# I2CIsoBreakoutV01.net
KiCad netlist of a schematic drawn in EAGLE
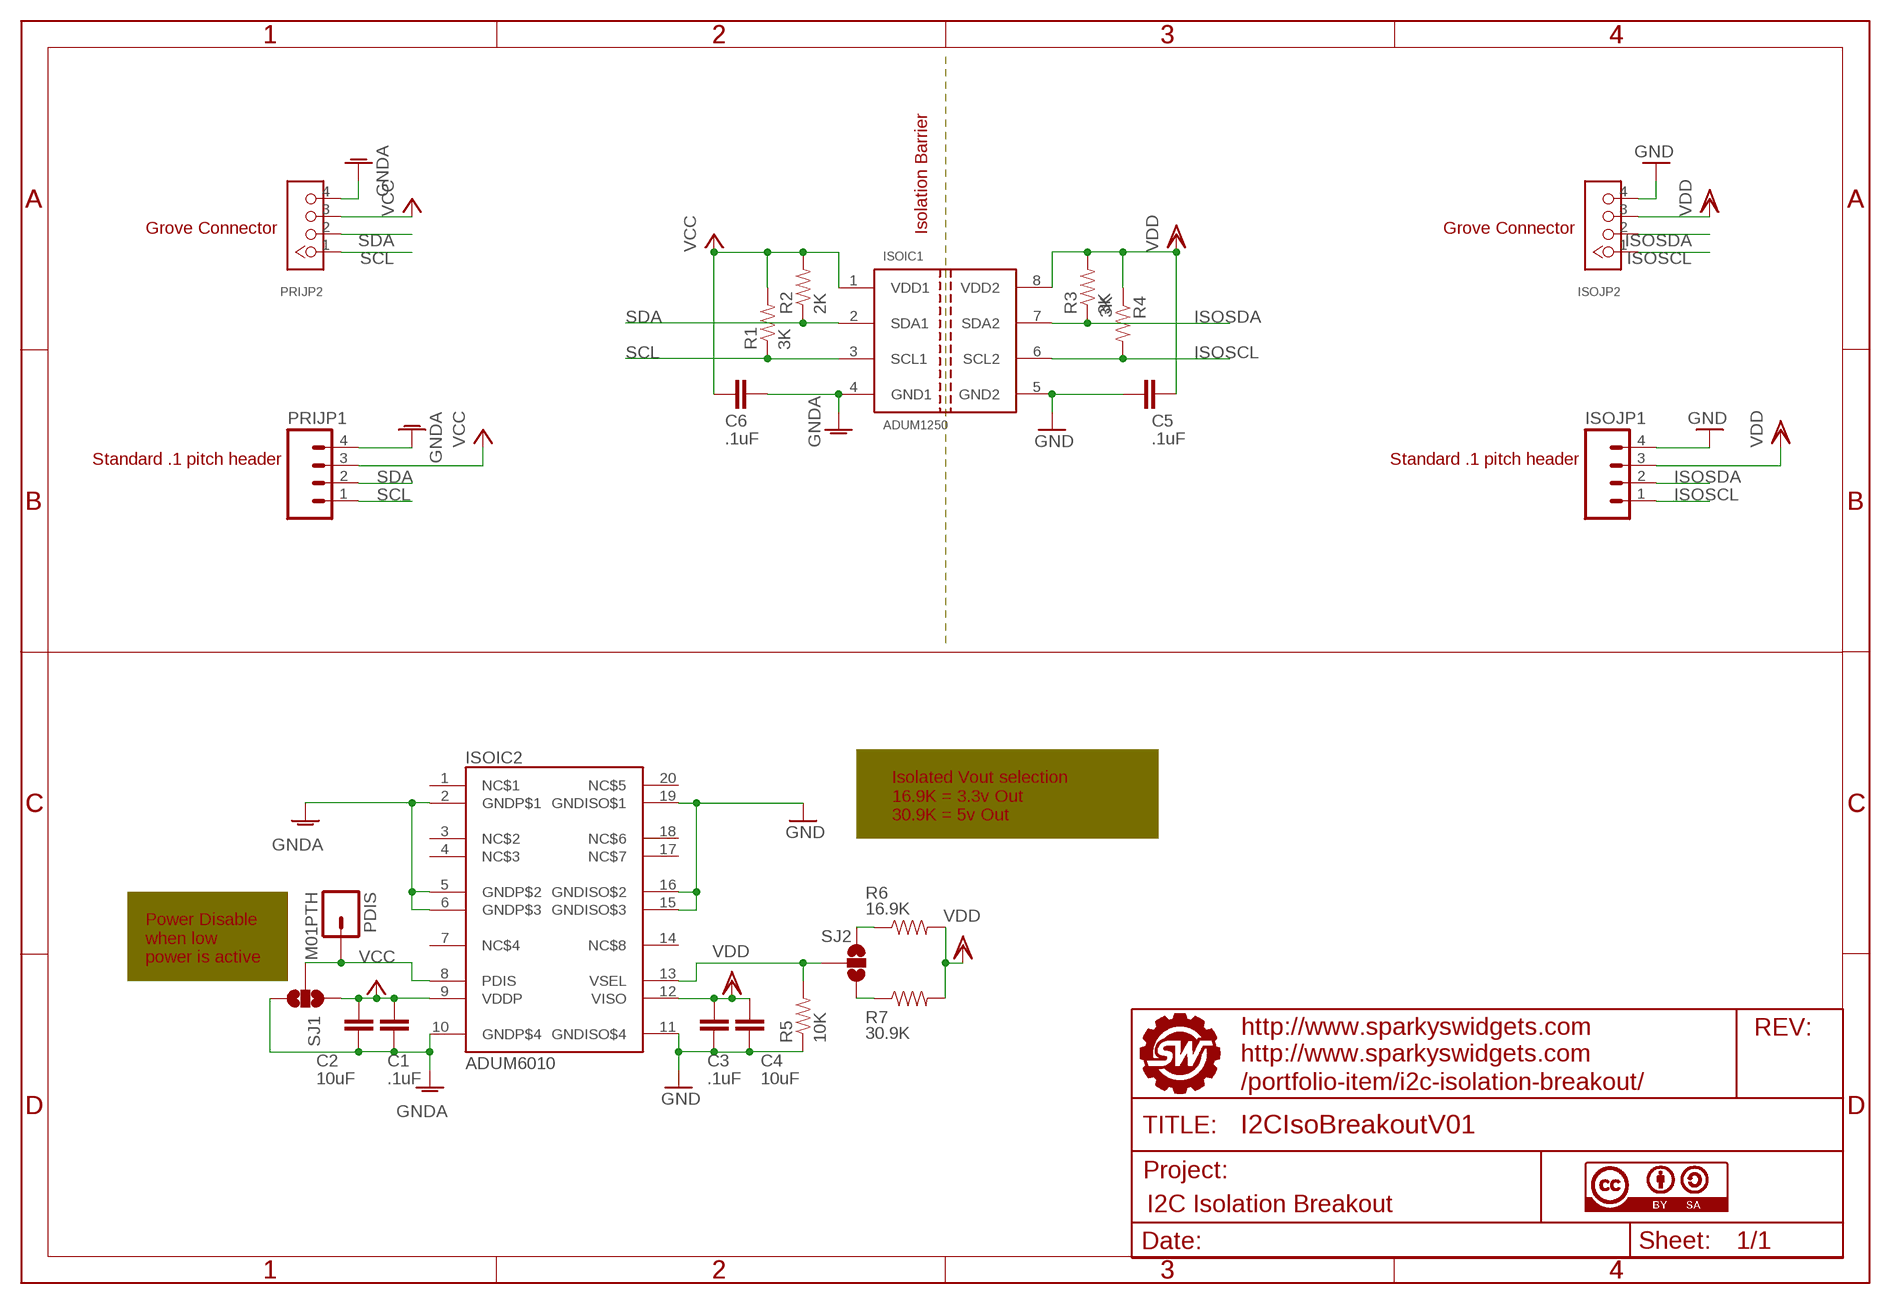
[diagram p0: schematic, sheet 1]

(export (version "E")
  (design (tool "Eeschema 10.0.6"))
  (components
    (comp (ref "C1")
      (value ".1uF")
      (footprint "eagle-import:0805")
      (libsource (lib "eagle-import") (part "CAP0805"))
    )
    (comp (ref "C2")
      (value "10uF")
      (footprint "eagle-import:0805")
      (libsource (lib "eagle-import") (part "CAP0805"))
    )
    (comp (ref "C3")
      (value ".1uF")
      (footprint "eagle-import:0805")
      (libsource (lib "eagle-import") (part "CAP0805"))
    )
    (comp (ref "C4")
      (value "10uF")
      (footprint "eagle-import:0805")
      (libsource (lib "eagle-import") (part "CAP0805"))
    )
    (comp (ref "C5")
      (value ".1uF")
      (footprint "eagle-import:0805")
      (libsource (lib "eagle-import") (part "CAP0805"))
    )
    (comp (ref "C6")
      (value ".1uF")
      (footprint "eagle-import:0805")
      (libsource (lib "eagle-import") (part "CAP0805"))
    )
    (comp (ref "ISOIC1")
      (value "ADUM1250")
      (footprint "eagle-import:SO08")
      (libsource (lib "eagle-import") (part "ADUM1250"))
    )
    (comp (ref "ISOIC2")
      (value "ADUM6010")
      (footprint "eagle-import:SSOP20")
      (libsource (lib "eagle-import") (part "ADUM6010"))
    )
    (comp (ref "ISOJP1")
      (value "M04PTH")
      (footprint "eagle-import:1X04")
      (libsource (lib "eagle-import") (part "M04PTH"))
    )
    (comp (ref "ISOJP2")
      (value "TWIG-4P-2.0-2.0")
      (footprint "eagle-import:4P-2.0")
      (libsource (lib "eagle-import") (part "TWIG-4P-2.0-2.0"))
    )
    (comp (ref "PDIS")
      (value "M01PTH")
      (footprint "eagle-import:1X01")
      (libsource (lib "eagle-import") (part "M01PTH"))
    )
    (comp (ref "PRIJP1")
      (value "M04PTH")
      (footprint "eagle-import:1X04")
      (libsource (lib "eagle-import") (part "M04PTH"))
    )
    (comp (ref "PRIJP2")
      (value "TWIG-4P-2.0-2.0")
      (footprint "eagle-import:4P-2.0")
      (libsource (lib "eagle-import") (part "TWIG-4P-2.0-2.0"))
    )
    (comp (ref "R1")
      (value "3K")
      (footprint "eagle-import:0805")
      (libsource (lib "eagle-import") (part "RESISTOR0805-RES"))
    )
    (comp (ref "R2")
      (value "2K")
      (footprint "eagle-import:0805")
      (libsource (lib "eagle-import") (part "RESISTOR0805-RES"))
    )
    (comp (ref "R3")
      (value "3K")
      (footprint "eagle-import:0805")
      (libsource (lib "eagle-import") (part "RESISTOR0805-RES"))
    )
    (comp (ref "R4")
      (value "3K")
      (footprint "eagle-import:0805")
      (libsource (lib "eagle-import") (part "RESISTOR0805-RES"))
    )
    (comp (ref "R5")
      (value "10K")
      (footprint "eagle-import:0805")
      (libsource (lib "eagle-import") (part "RESISTOR0805-RES"))
    )
    (comp (ref "R6")
      (value "16.9K")
      (footprint "eagle-import:0805")
      (libsource (lib "eagle-import") (part "RESISTOR0805-RES"))
    )
    (comp (ref "R7")
      (value "30.9K")
      (footprint "eagle-import:0805")
      (libsource (lib "eagle-import") (part "RESISTOR0805-RES"))
    )
    (comp (ref "SJ1")
      (value "SOLDERJUMPER_2WAYPASTE2&3")
      (footprint "eagle-import:SJ_3_PASTE2&3")
      (libsource (lib "eagle-import") (part "SOLDERJUMPER_2WAYPASTE2&3"))
    )
    (comp (ref "SJ2")
      (value "SOLDERJUMPER_2WAYPASTE2&3")
      (footprint "eagle-import:SJ_3_PASTE2&3")
      (libsource (lib "eagle-import") (part "SOLDERJUMPER_2WAYPASTE2&3"))
    )
    (comp (ref "U$1")
      (value "FRAME_ISOI2CBREAKOUT")
      (footprint "eagle-import:SWPCBLOGOWITHINFO")
      (libsource (lib "eagle-import") (part "FRAME_ISOI2CBREAKOUT"))
    )
    (comp (ref "U$2")
      (value "CC-BY-SA")
      (footprint "eagle-import:CC-BY-SA")
      (libsource (lib "eagle-import") (part "CC-BY-SA"))
    )
  )
  (nets
    (net (code "1") (name "/ISOSCL") (class "Default")
      (node (ref "ISOIC1") (pin "6") (pinfunction "SCL2_6") (pintype "bidirectional"))
      (node (ref "ISOJP1") (pin "1") (pinfunction "1_1") (pintype "passive"))
      (node (ref "ISOJP2") (pin "1") (pinfunction "1_1") (pintype "bidirectional"))
      (node (ref "R4") (pin "2") (pinfunction "2_2") (pintype "passive"))
    )
    (net (code "2") (name "/ISOSDA") (class "Default")
      (node (ref "ISOIC1") (pin "7") (pinfunction "SDA2_7") (pintype "bidirectional"))
      (node (ref "ISOJP1") (pin "2") (pinfunction "2_2") (pintype "passive"))
      (node (ref "ISOJP2") (pin "2") (pinfunction "2_2") (pintype "bidirectional"))
      (node (ref "R3") (pin "1") (pinfunction "1_1") (pintype "passive"))
    )
    (net (code "3") (name "/SCL") (class "Default")
      (node (ref "ISOIC1") (pin "3") (pinfunction "SCL1_3") (pintype "bidirectional"))
      (node (ref "PRIJP1") (pin "1") (pinfunction "1_1") (pintype "passive"))
      (node (ref "PRIJP2") (pin "1") (pinfunction "1_1") (pintype "bidirectional"))
      (node (ref "R1") (pin "1") (pinfunction "1_1") (pintype "passive"))
    )
    (net (code "4") (name "/SDA") (class "Default")
      (node (ref "ISOIC1") (pin "2") (pinfunction "SDA1_2") (pintype "bidirectional"))
      (node (ref "PRIJP1") (pin "2") (pinfunction "2_2") (pintype "passive"))
      (node (ref "PRIJP2") (pin "2") (pinfunction "2_2") (pintype "bidirectional"))
      (node (ref "R2") (pin "1") (pinfunction "1_1") (pintype "passive"))
    )
    (net (code "5") (name "GND") (class "Default")
      (node (ref "C3") (pin "2") (pinfunction "2_2") (pintype "passive"))
      (node (ref "C4") (pin "2") (pinfunction "2_2") (pintype "passive"))
      (node (ref "C5") (pin "1") (pinfunction "1_1") (pintype "passive"))
      (node (ref "ISOIC1") (pin "5") (pinfunction "GND2_5") (pintype "power_in"))
      (node (ref "ISOIC2") (pin "11") (pinfunction "GNDISO$4_11") (pintype "power_in"))
      (node (ref "ISOIC2") (pin "15") (pinfunction "GNDISO$3_15") (pintype "power_in"))
      (node (ref "ISOIC2") (pin "16") (pinfunction "GNDISO$2_16") (pintype "power_in"))
      (node (ref "ISOIC2") (pin "19") (pinfunction "GNDISO$1_19") (pintype "power_in"))
      (node (ref "ISOJP1") (pin "4") (pinfunction "4_4") (pintype "passive"))
      (node (ref "ISOJP2") (pin "4") (pinfunction "4_4") (pintype "bidirectional"))
      (node (ref "R5") (pin "1") (pinfunction "1_1") (pintype "passive"))
    )
    (net (code "6") (name "GNDA") (class "Default")
      (node (ref "C1") (pin "2") (pinfunction "2_2") (pintype "passive"))
      (node (ref "C2") (pin "2") (pinfunction "2_2") (pintype "passive"))
      (node (ref "C6") (pin "1") (pinfunction "1_1") (pintype "passive"))
      (node (ref "ISOIC1") (pin "4") (pinfunction "GND1_4") (pintype "power_in"))
      (node (ref "ISOIC2") (pin "10") (pinfunction "GNDP$4_10") (pintype "power_in"))
      (node (ref "ISOIC2") (pin "2") (pinfunction "GNDP$1_2") (pintype "power_in"))
      (node (ref "ISOIC2") (pin "5") (pinfunction "GNDP$2_5") (pintype "power_in"))
      (node (ref "ISOIC2") (pin "6") (pinfunction "GNDP$3_6") (pintype "power_in"))
      (node (ref "PRIJP1") (pin "4") (pinfunction "4_4") (pintype "passive"))
      (node (ref "PRIJP2") (pin "4") (pinfunction "4_4") (pintype "bidirectional"))
      (node (ref "SJ1") (pin "3") (pinfunction "3_3") (pintype "passive"))
    )
    (net (code "7") (name "Net-(ISOIC2-PDIS)") (class "Default")
      (node (ref "ISOIC2") (pin "8") (pinfunction "PDIS_8") (pintype "input"))
      (node (ref "PDIS") (pin "1") (pinfunction "1_1") (pintype "passive"))
      (node (ref "SJ1") (pin "2") (pinfunction "2_2") (pintype "passive"))
    )
    (net (code "8") (name "Net-(ISOIC2-VSEL)") (class "Default")
      (node (ref "ISOIC2") (pin "13") (pinfunction "VSEL_13") (pintype "input"))
      (node (ref "R5") (pin "2") (pinfunction "2_2") (pintype "passive"))
      (node (ref "SJ2") (pin "2") (pinfunction "2_2") (pintype "passive"))
    )
    (net (code "9") (name "Net-(R6-Pad1)") (class "Default")
      (node (ref "R6") (pin "1") (pinfunction "1_1") (pintype "passive"))
      (node (ref "SJ2") (pin "1") (pinfunction "1_1") (pintype "passive"))
    )
    (net (code "10") (name "Net-(R7-Pad1)") (class "Default")
      (node (ref "R7") (pin "1") (pinfunction "1_1") (pintype "passive"))
      (node (ref "SJ2") (pin "3") (pinfunction "3_3") (pintype "passive"))
    )
    (net (code "11") (name "VCC") (class "Default")
      (node (ref "C1") (pin "1") (pinfunction "1_1") (pintype "passive"))
      (node (ref "C2") (pin "1") (pinfunction "1_1") (pintype "passive"))
      (node (ref "C6") (pin "2") (pinfunction "2_2") (pintype "passive"))
      (node (ref "ISOIC1") (pin "1") (pinfunction "VDD1_1") (pintype "power_in"))
      (node (ref "ISOIC2") (pin "9") (pinfunction "VDDP_9") (pintype "power_in"))
      (node (ref "PRIJP1") (pin "3") (pinfunction "3_3") (pintype "passive"))
      (node (ref "PRIJP2") (pin "3") (pinfunction "3_3") (pintype "bidirectional"))
      (node (ref "R1") (pin "2") (pinfunction "2_2") (pintype "passive"))
      (node (ref "R2") (pin "2") (pinfunction "2_2") (pintype "passive"))
      (node (ref "SJ1") (pin "1") (pinfunction "1_1") (pintype "passive"))
    )
    (net (code "12") (name "VDD") (class "Default")
      (node (ref "C3") (pin "1") (pinfunction "1_1") (pintype "passive"))
      (node (ref "C4") (pin "1") (pinfunction "1_1") (pintype "passive"))
      (node (ref "C5") (pin "2") (pinfunction "2_2") (pintype "passive"))
      (node (ref "ISOIC1") (pin "8") (pinfunction "VDD2_8") (pintype "power_in"))
      (node (ref "ISOIC2") (pin "12") (pinfunction "VISO_12") (pintype "power_in"))
      (node (ref "ISOJP1") (pin "3") (pinfunction "3_3") (pintype "passive"))
      (node (ref "ISOJP2") (pin "3") (pinfunction "3_3") (pintype "bidirectional"))
      (node (ref "R3") (pin "2") (pinfunction "2_2") (pintype "passive"))
      (node (ref "R4") (pin "1") (pinfunction "1_1") (pintype "passive"))
      (node (ref "R6") (pin "2") (pinfunction "2_2") (pintype "passive"))
      (node (ref "R7") (pin "2") (pinfunction "2_2") (pintype "passive"))
    )
    (net (code "13") (name "unconnected-(ISOIC2-NC$1-Pad1)") (class "Default")
      (node (ref "ISOIC2") (pin "1") (pinfunction "NC$1_1") (pintype "no_connect"))
    )
    (net (code "14") (name "unconnected-(ISOIC2-NC$2-Pad3)") (class "Default")
      (node (ref "ISOIC2") (pin "3") (pinfunction "NC$2_3") (pintype "no_connect"))
    )
    (net (code "15") (name "unconnected-(ISOIC2-NC$3-Pad4)") (class "Default")
      (node (ref "ISOIC2") (pin "4") (pinfunction "NC$3_4") (pintype "no_connect"))
    )
    (net (code "16") (name "unconnected-(ISOIC2-NC$4-Pad7)") (class "Default")
      (node (ref "ISOIC2") (pin "7") (pinfunction "NC$4_7") (pintype "no_connect"))
    )
    (net (code "17") (name "unconnected-(ISOIC2-NC$5-Pad20)") (class "Default")
      (node (ref "ISOIC2") (pin "20") (pinfunction "NC$5_20") (pintype "no_connect"))
    )
    (net (code "18") (name "unconnected-(ISOIC2-NC$6-Pad18)") (class "Default")
      (node (ref "ISOIC2") (pin "18") (pinfunction "NC$6_18") (pintype "no_connect"))
    )
    (net (code "19") (name "unconnected-(ISOIC2-NC$7-Pad17)") (class "Default")
      (node (ref "ISOIC2") (pin "17") (pinfunction "NC$7_17") (pintype "no_connect"))
    )
    (net (code "20") (name "unconnected-(ISOIC2-NC$8-Pad14)") (class "Default")
      (node (ref "ISOIC2") (pin "14") (pinfunction "NC$8_14") (pintype "no_connect"))
    )
  )
)
